# main.net
KiCad netlist of a schematic drawn in EAGLE
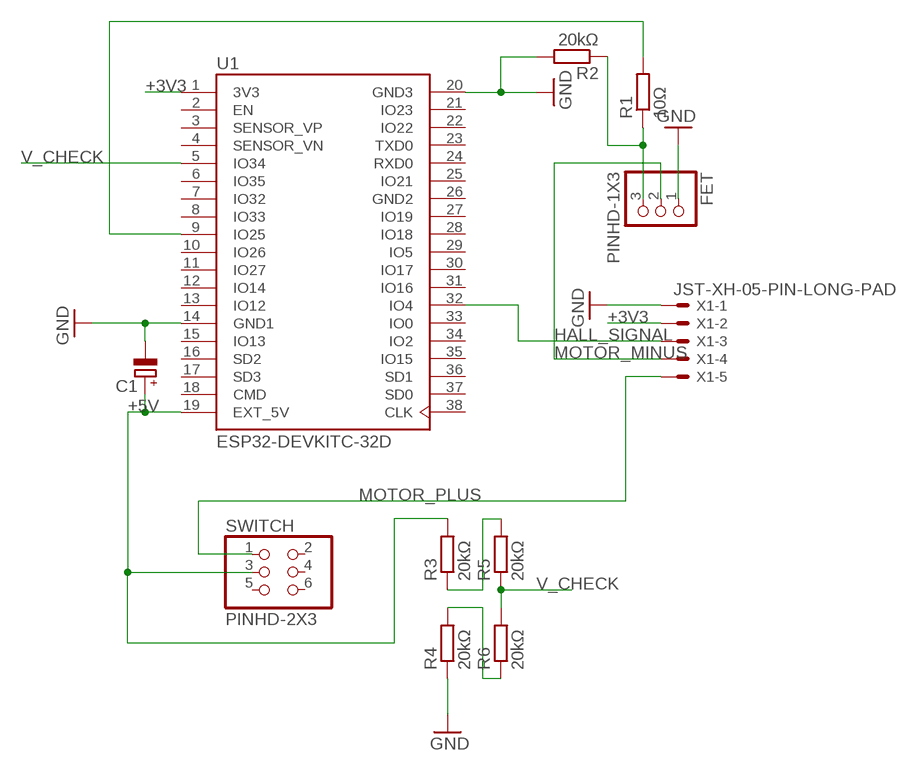
[diagram p0: schematic, sheet 1]

(export (version "E")
  (design (tool "Eeschema 10.0.6"))
  (components
    (comp (ref "C1")
      (value "CPOL-EUE5-10.5")
      (footprint "eagle-import:E5-10,5")
      (libsource (lib "eagle-import") (part "CPOL-EUE5-10.5"))
    )
    (comp (ref "FET")
      (value "PINHD-1X3")
      (footprint "eagle-import:1X03")
      (libsource (lib "eagle-import") (part "PINHD-1X3"))
    )
    (comp (ref "R1")
      (value "10Ω")
      (footprint "eagle-import:0207_10")
      (libsource (lib "eagle-import") (part "R-EU_0207/10"))
    )
    (comp (ref "R2")
      (value "20kΩ")
      (footprint "eagle-import:0207_10")
      (libsource (lib "eagle-import") (part "R-EU_0207/10"))
    )
    (comp (ref "R3")
      (value "20kΩ")
      (footprint "eagle-import:0207_10")
      (libsource (lib "eagle-import") (part "R-EU_0207/10"))
    )
    (comp (ref "R4")
      (value "20kΩ")
      (footprint "eagle-import:0207_10")
      (libsource (lib "eagle-import") (part "R-EU_0207/10"))
    )
    (comp (ref "R5")
      (value "20kΩ")
      (footprint "eagle-import:0207_10")
      (libsource (lib "eagle-import") (part "R-EU_0207/10"))
    )
    (comp (ref "R6")
      (value "20kΩ")
      (footprint "eagle-import:0207_10")
      (libsource (lib "eagle-import") (part "R-EU_0207/10"))
    )
    (comp (ref "SWITCH")
      (value "PINHD-2X3")
      (footprint "eagle-import:2X03")
      (libsource (lib "eagle-import") (part "PINHD-2X3"))
    )
    (comp (ref "U1")
      (value "ESP32-DEVKITC-32D")
      (footprint "eagle-import:MODULE_ESP32-DEVKITC-32D")
      (fields (field (name "MANUFACTURER") "Espressif Systems"))
      (libsource (lib "eagle-import") (part "ESP32-DEVKITC-32D"))
    )
    (comp (ref "X1")
      (value "JST-XH-05-PIN-LONG-PAD")
      (footprint "eagle-import:JST-XH-05-PACKAGE-LONG-PAD")
      (libsource (lib "eagle-import") (part "JST-XH-05-PIN-LONG-PAD"))
    )
  )
  (nets
    (net (code "1") (name "/+3V3") (class "Default")
      (node (ref "U1") (pin "1") (pinfunction "3V3_1") (pintype "power_in"))
      (node (ref "X1") (pin "2") (pinfunction "S_2") (pintype "passive"))
    )
    (net (code "2") (name "/+5V") (class "Default")
      (node (ref "C1") (pin "+") (pinfunction "+_+") (pintype "passive"))
      (node (ref "R3") (pin "2") (pinfunction "2_2") (pintype "passive"))
      (node (ref "SWITCH") (pin "3") (pinfunction "3_3") (pintype "passive"))
      (node (ref "U1") (pin "19") (pinfunction "EXT_5V_19") (pintype "power_in"))
    )
    (net (code "3") (name "/GND2") (class "Default")
      (node (ref "U1") (pin "26") (pinfunction "GND2_26") (pintype "power_in"))
    )
    (net (code "4") (name "/HALL_SIGNAL") (class "Default")
      (node (ref "U1") (pin "32") (pinfunction "IO4_32") (pintype "bidirectional"))
      (node (ref "X1") (pin "3") (pinfunction "S_3") (pintype "passive"))
    )
    (net (code "5") (name "/MOTOR_MINUS") (class "Default")
      (node (ref "FET") (pin "2") (pinfunction "2_2") (pintype "passive"))
      (node (ref "X1") (pin "4") (pinfunction "S_4") (pintype "passive"))
    )
    (net (code "6") (name "/MOTOR_PLUS") (class "Default")
      (node (ref "SWITCH") (pin "1") (pinfunction "1_1") (pintype "passive"))
      (node (ref "X1") (pin "5") (pinfunction "S_5") (pintype "passive"))
    )
    (net (code "7") (name "/V_CHECK") (class "Default")
      (node (ref "R5") (pin "1") (pinfunction "1_1") (pintype "passive"))
      (node (ref "R6") (pin "2") (pinfunction "2_2") (pintype "passive"))
      (node (ref "U1") (pin "5") (pinfunction "IO34_5") (pintype "bidirectional"))
    )
    (net (code "8") (name "GND") (class "Default")
      (node (ref "C1") (pin "-") (pinfunction "-_-") (pintype "passive"))
      (node (ref "FET") (pin "1") (pinfunction "1_1") (pintype "passive"))
      (node (ref "R2") (pin "2") (pinfunction "2_2") (pintype "passive"))
      (node (ref "R4") (pin "1") (pinfunction "1_1") (pintype "passive"))
      (node (ref "U1") (pin "14") (pinfunction "GND1_14") (pintype "power_in"))
      (node (ref "U1") (pin "20") (pinfunction "GND3_20") (pintype "power_in"))
      (node (ref "X1") (pin "1") (pinfunction "S_1") (pintype "passive"))
    )
    (net (code "9") (name "Net-(FET-Pad3)") (class "Default")
      (node (ref "FET") (pin "3") (pinfunction "3_3") (pintype "passive"))
      (node (ref "R1") (pin "1") (pinfunction "1_1") (pintype "passive"))
      (node (ref "R2") (pin "1") (pinfunction "1_1") (pintype "passive"))
    )
    (net (code "10") (name "Net-(R3-Pad1)") (class "Default")
      (node (ref "R3") (pin "1") (pinfunction "1_1") (pintype "passive"))
      (node (ref "R5") (pin "2") (pinfunction "2_2") (pintype "passive"))
    )
    (net (code "11") (name "Net-(R4-Pad2)") (class "Default")
      (node (ref "R4") (pin "2") (pinfunction "2_2") (pintype "passive"))
      (node (ref "R6") (pin "1") (pinfunction "1_1") (pintype "passive"))
    )
    (net (code "12") (name "Net-(U1-IO25)") (class "Default")
      (node (ref "R1") (pin "2") (pinfunction "2_2") (pintype "passive"))
      (node (ref "U1") (pin "9") (pinfunction "IO25_9") (pintype "bidirectional"))
    )
    (net (code "13") (name "unconnected-(SWITCH-Pad2)") (class "Default")
      (node (ref "SWITCH") (pin "2") (pinfunction "2_2") (pintype "passive"))
    )
    (net (code "14") (name "unconnected-(SWITCH-Pad4)") (class "Default")
      (node (ref "SWITCH") (pin "4") (pinfunction "4_4") (pintype "passive"))
    )
    (net (code "15") (name "unconnected-(SWITCH-Pad5)") (class "Default")
      (node (ref "SWITCH") (pin "5") (pinfunction "5_5") (pintype "passive"))
    )
    (net (code "16") (name "unconnected-(SWITCH-Pad6)") (class "Default")
      (node (ref "SWITCH") (pin "6") (pinfunction "6_6") (pintype "passive"))
    )
    (net (code "17") (name "unconnected-(U1-CLK-Pad38)") (class "Default")
      (node (ref "U1") (pin "38") (pinfunction "CLK_38") (pintype "input"))
    )
    (net (code "18") (name "unconnected-(U1-CMD-Pad18)") (class "Default")
      (node (ref "U1") (pin "18") (pinfunction "CMD_18") (pintype "bidirectional"))
    )
    (net (code "19") (name "unconnected-(U1-EN-Pad2)") (class "Default")
      (node (ref "U1") (pin "2") (pinfunction "EN_2") (pintype "input"))
    )
    (net (code "20") (name "unconnected-(U1-IO0-Pad33)") (class "Default")
      (node (ref "U1") (pin "33") (pinfunction "IO0_33") (pintype "bidirectional"))
    )
    (net (code "21") (name "unconnected-(U1-IO2-Pad34)") (class "Default")
      (node (ref "U1") (pin "34") (pinfunction "IO2_34") (pintype "bidirectional"))
    )
    (net (code "22") (name "unconnected-(U1-IO5-Pad29)") (class "Default")
      (node (ref "U1") (pin "29") (pinfunction "IO5_29") (pintype "bidirectional"))
    )
    (net (code "23") (name "unconnected-(U1-IO12-Pad13)") (class "Default")
      (node (ref "U1") (pin "13") (pinfunction "IO12_13") (pintype "bidirectional"))
    )
    (net (code "24") (name "unconnected-(U1-IO13-Pad15)") (class "Default")
      (node (ref "U1") (pin "15") (pinfunction "IO13_15") (pintype "bidirectional"))
    )
    (net (code "25") (name "unconnected-(U1-IO14-Pad12)") (class "Default")
      (node (ref "U1") (pin "12") (pinfunction "IO14_12") (pintype "bidirectional"))
    )
    (net (code "26") (name "unconnected-(U1-IO15-Pad35)") (class "Default")
      (node (ref "U1") (pin "35") (pinfunction "IO15_35") (pintype "bidirectional"))
    )
    (net (code "27") (name "unconnected-(U1-IO16-Pad31)") (class "Default")
      (node (ref "U1") (pin "31") (pinfunction "IO16_31") (pintype "bidirectional"))
    )
    (net (code "28") (name "unconnected-(U1-IO17-Pad30)") (class "Default")
      (node (ref "U1") (pin "30") (pinfunction "IO17_30") (pintype "bidirectional"))
    )
    (net (code "29") (name "unconnected-(U1-IO18-Pad28)") (class "Default")
      (node (ref "U1") (pin "28") (pinfunction "IO18_28") (pintype "bidirectional"))
    )
    (net (code "30") (name "unconnected-(U1-IO19-Pad27)") (class "Default")
      (node (ref "U1") (pin "27") (pinfunction "IO19_27") (pintype "bidirectional"))
    )
    (net (code "31") (name "unconnected-(U1-IO21-Pad25)") (class "Default")
      (node (ref "U1") (pin "25") (pinfunction "IO21_25") (pintype "bidirectional"))
    )
    (net (code "32") (name "unconnected-(U1-IO22-Pad22)") (class "Default")
      (node (ref "U1") (pin "22") (pinfunction "IO22_22") (pintype "bidirectional"))
    )
    (net (code "33") (name "unconnected-(U1-IO23-Pad21)") (class "Default")
      (node (ref "U1") (pin "21") (pinfunction "IO23_21") (pintype "bidirectional"))
    )
    (net (code "34") (name "unconnected-(U1-IO26-Pad10)") (class "Default")
      (node (ref "U1") (pin "10") (pinfunction "IO26_10") (pintype "bidirectional"))
    )
    (net (code "35") (name "unconnected-(U1-IO27-Pad11)") (class "Default")
      (node (ref "U1") (pin "11") (pinfunction "IO27_11") (pintype "bidirectional"))
    )
    (net (code "36") (name "unconnected-(U1-IO32-Pad7)") (class "Default")
      (node (ref "U1") (pin "7") (pinfunction "IO32_7") (pintype "bidirectional"))
    )
    (net (code "37") (name "unconnected-(U1-IO33-Pad8)") (class "Default")
      (node (ref "U1") (pin "8") (pinfunction "IO33_8") (pintype "bidirectional"))
    )
    (net (code "38") (name "unconnected-(U1-IO35-Pad6)") (class "Default")
      (node (ref "U1") (pin "6") (pinfunction "IO35_6") (pintype "bidirectional"))
    )
    (net (code "39") (name "unconnected-(U1-RXD0-Pad24)") (class "Default")
      (node (ref "U1") (pin "24") (pinfunction "RXD0_24") (pintype "input"))
    )
    (net (code "40") (name "unconnected-(U1-SD0-Pad37)") (class "Default")
      (node (ref "U1") (pin "37") (pinfunction "SD0_37") (pintype "bidirectional"))
    )
    (net (code "41") (name "unconnected-(U1-SD1-Pad36)") (class "Default")
      (node (ref "U1") (pin "36") (pinfunction "SD1_36") (pintype "bidirectional"))
    )
    (net (code "42") (name "unconnected-(U1-SD2-Pad16)") (class "Default")
      (node (ref "U1") (pin "16") (pinfunction "SD2_16") (pintype "bidirectional"))
    )
    (net (code "43") (name "unconnected-(U1-SD3-Pad17)") (class "Default")
      (node (ref "U1") (pin "17") (pinfunction "SD3_17") (pintype "bidirectional"))
    )
    (net (code "44") (name "unconnected-(U1-SENSOR_VN-Pad4)") (class "Default")
      (node (ref "U1") (pin "4") (pinfunction "SENSOR_VN_4") (pintype "input"))
    )
    (net (code "45") (name "unconnected-(U1-SENSOR_VP-Pad3)") (class "Default")
      (node (ref "U1") (pin "3") (pinfunction "SENSOR_VP_3") (pintype "input"))
    )
    (net (code "46") (name "unconnected-(U1-TXD0-Pad23)") (class "Default")
      (node (ref "U1") (pin "23") (pinfunction "TXD0_23") (pintype "output"))
    )
  )
)
